# SPI_ESP12E.net
KiCad netlist of a schematic drawn in EAGLE
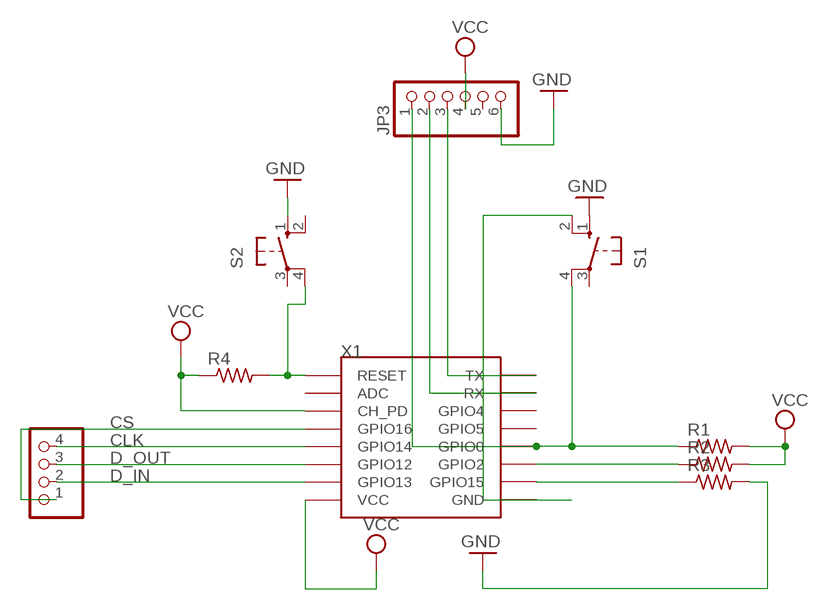
[diagram p0: schematic, sheet 1]

(export (version "E")
  (design (tool "Eeschema 10.0.6"))
  (components
    (comp (ref "JP3")
      (value "PINHD-1X6B")
      (footprint "eagle-import:1X06-BIG")
      (libsource (lib "eagle-import") (part "PINHD-1X6B"))
    )
    (comp (ref "R1")
      (value "R-US_0204/7")
      (footprint "eagle-import:0204_7")
      (libsource (lib "eagle-import") (part "R-US_0204/7"))
    )
    (comp (ref "R2")
      (value "R-US_0204/7")
      (footprint "eagle-import:0204_7")
      (libsource (lib "eagle-import") (part "R-US_0204/7"))
    )
    (comp (ref "R3")
      (value "R-US_0204/7")
      (footprint "eagle-import:0204_7")
      (libsource (lib "eagle-import") (part "R-US_0204/7"))
    )
    (comp (ref "R4")
      (value "R-US_0204/5")
      (footprint "eagle-import:0204_5")
      (libsource (lib "eagle-import") (part "R-US_0204/5"))
    )
    (comp (ref "S1")
      (value "10-XX")
      (footprint "eagle-import:B3F-10XX")
      (fields (field (name "MPN") "B3F-1000"))
      (libsource (lib "eagle-import") (part "10-XX"))
    )
    (comp (ref "S2")
      (value "10-XX")
      (footprint "eagle-import:B3F-10XX")
      (fields (field (name "MPN") "B3F-1000"))
      (libsource (lib "eagle-import") (part "10-XX"))
    )
    (comp (ref "SPI")
      (value "PINHD-1X4")
      (footprint "eagle-import:1X04")
      (libsource (lib "eagle-import") (part "PINHD-1X4"))
    )
    (comp (ref "X1")
      (value "ESP12SMD")
      (footprint "eagle-import:ESP12-SMD")
      (libsource (lib "eagle-import") (part "ESP12SMD"))
    )
  )
  (nets
    (net (code "1") (name "CLK") (class "Default")
      (node (ref "SPI") (pin "4") (pinfunction "4_4") (pintype "passive"))
      (node (ref "X1") (pin "GPIO14") (pinfunction "GPIO14_GPIO14") (pintype "bidirectional"))
    )
    (net (code "2") (name "CS") (class "Default")
      (node (ref "SPI") (pin "1") (pinfunction "1_1") (pintype "passive"))
      (node (ref "X1") (pin "GPIO16") (pinfunction "GPIO16_GPIO16") (pintype "bidirectional"))
    )
    (net (code "3") (name "D_IN") (class "Default")
      (node (ref "SPI") (pin "2") (pinfunction "2_2") (pintype "passive"))
      (node (ref "X1") (pin "GPIO13") (pinfunction "GPIO13_GPIO13") (pintype "bidirectional"))
    )
    (net (code "4") (name "D_OUT") (class "Default")
      (node (ref "SPI") (pin "3") (pinfunction "3_3") (pintype "passive"))
      (node (ref "X1") (pin "GPIO12") (pinfunction "GPIO12_GPIO12") (pintype "bidirectional"))
    )
    (net (code "5") (name "GND") (class "Default")
      (node (ref "JP3") (pin "6") (pinfunction "6_6") (pintype "passive"))
      (node (ref "R3") (pin "2") (pinfunction "2_2") (pintype "passive"))
      (node (ref "S1") (pin "1") (pinfunction "S_1") (pintype "passive"))
      (node (ref "S2") (pin "1") (pinfunction "S_1") (pintype "passive"))
    )
    (net (code "6") (name "Net-(R2-Pad1)") (class "Default")
      (node (ref "R2") (pin "1") (pinfunction "1_1") (pintype "passive"))
      (node (ref "X1") (pin "GPIO2") (pinfunction "GPIO2_GPIO2") (pintype "bidirectional"))
    )
    (net (code "7") (name "Net-(R3-Pad1)") (class "Default")
      (node (ref "R3") (pin "1") (pinfunction "1_1") (pintype "passive"))
      (node (ref "X1") (pin "GPIO15") (pinfunction "GPIO15_GPIO15") (pintype "bidirectional"))
    )
    (net (code "8") (name "Net-(S1-P1)") (class "Default")
      (node (ref "JP3") (pin "1") (pinfunction "1_1") (pintype "passive"))
      (node (ref "R1") (pin "1") (pinfunction "1_1") (pintype "passive"))
      (node (ref "S1") (pin "4") (pinfunction "P1_4") (pintype "passive"))
      (node (ref "X1") (pin "GPIO0") (pinfunction "GPIO0_GPIO0") (pintype "bidirectional"))
    )
    (net (code "9") (name "Net-(S1-S1)") (class "Default")
      (node (ref "S1") (pin "2") (pinfunction "S1_2") (pintype "passive"))
      (node (ref "X1") (pin "GND") (pinfunction "GND_GND") (pintype "bidirectional"))
    )
    (net (code "10") (name "Net-(S2-P1)") (class "Default")
      (node (ref "R4") (pin "2") (pinfunction "2_2") (pintype "passive"))
      (node (ref "S2") (pin "4") (pinfunction "P1_4") (pintype "passive"))
      (node (ref "X1") (pin "RESET") (pinfunction "RESET_RESET") (pintype "bidirectional"))
    )
    (net (code "11") (name "Net-(X1-RX)") (class "Default")
      (node (ref "JP3") (pin "2") (pinfunction "2_2") (pintype "passive"))
      (node (ref "X1") (pin "RXD0") (pinfunction "RX_RXD0") (pintype "bidirectional"))
    )
    (net (code "12") (name "Net-(X1-TX)") (class "Default")
      (node (ref "JP3") (pin "3") (pinfunction "3_3") (pintype "passive"))
      (node (ref "X1") (pin "TXD0") (pinfunction "TX_TXD0") (pintype "bidirectional"))
    )
    (net (code "13") (name "VCC") (class "Default")
      (node (ref "JP3") (pin "4") (pinfunction "4_4") (pintype "passive"))
      (node (ref "R1") (pin "2") (pinfunction "2_2") (pintype "passive"))
      (node (ref "R2") (pin "2") (pinfunction "2_2") (pintype "passive"))
      (node (ref "R4") (pin "1") (pinfunction "1_1") (pintype "passive"))
      (node (ref "X1") (pin "CH_PD") (pinfunction "CH_PD_CH_PD") (pintype "bidirectional"))
      (node (ref "X1") (pin "VCC") (pinfunction "VCC_VCC") (pintype "bidirectional"))
    )
    (net (code "14") (name "unconnected-(JP3-Pad5)") (class "Default")
      (node (ref "JP3") (pin "5") (pinfunction "5_5") (pintype "passive"))
    )
    (net (code "15") (name "unconnected-(S1-P-Pad3)") (class "Default")
      (node (ref "S1") (pin "3") (pinfunction "P_3") (pintype "passive"))
    )
    (net (code "16") (name "unconnected-(S2-P-Pad3)") (class "Default")
      (node (ref "S2") (pin "3") (pinfunction "P_3") (pintype "passive"))
    )
    (net (code "17") (name "unconnected-(S2-S1-Pad2)") (class "Default")
      (node (ref "S2") (pin "2") (pinfunction "S1_2") (pintype "passive"))
    )
    (net (code "18") (name "unconnected-(X1-PadADC)") (class "Default")
      (node (ref "X1") (pin "ADC") (pinfunction "ADC_ADC") (pintype "bidirectional"))
    )
    (net (code "19") (name "unconnected-(X1-PadGPIO4)") (class "Default")
      (node (ref "X1") (pin "GPIO4") (pinfunction "GPIO4_GPIO4") (pintype "bidirectional"))
    )
    (net (code "20") (name "unconnected-(X1-PadGPIO5)") (class "Default")
      (node (ref "X1") (pin "GPIO5") (pinfunction "GPIO5_GPIO5") (pintype "bidirectional"))
    )
  )
)
